# 01_Touch_Sensing_Keys.net
KiCad netlist of a schematic drawn in Altium Designer
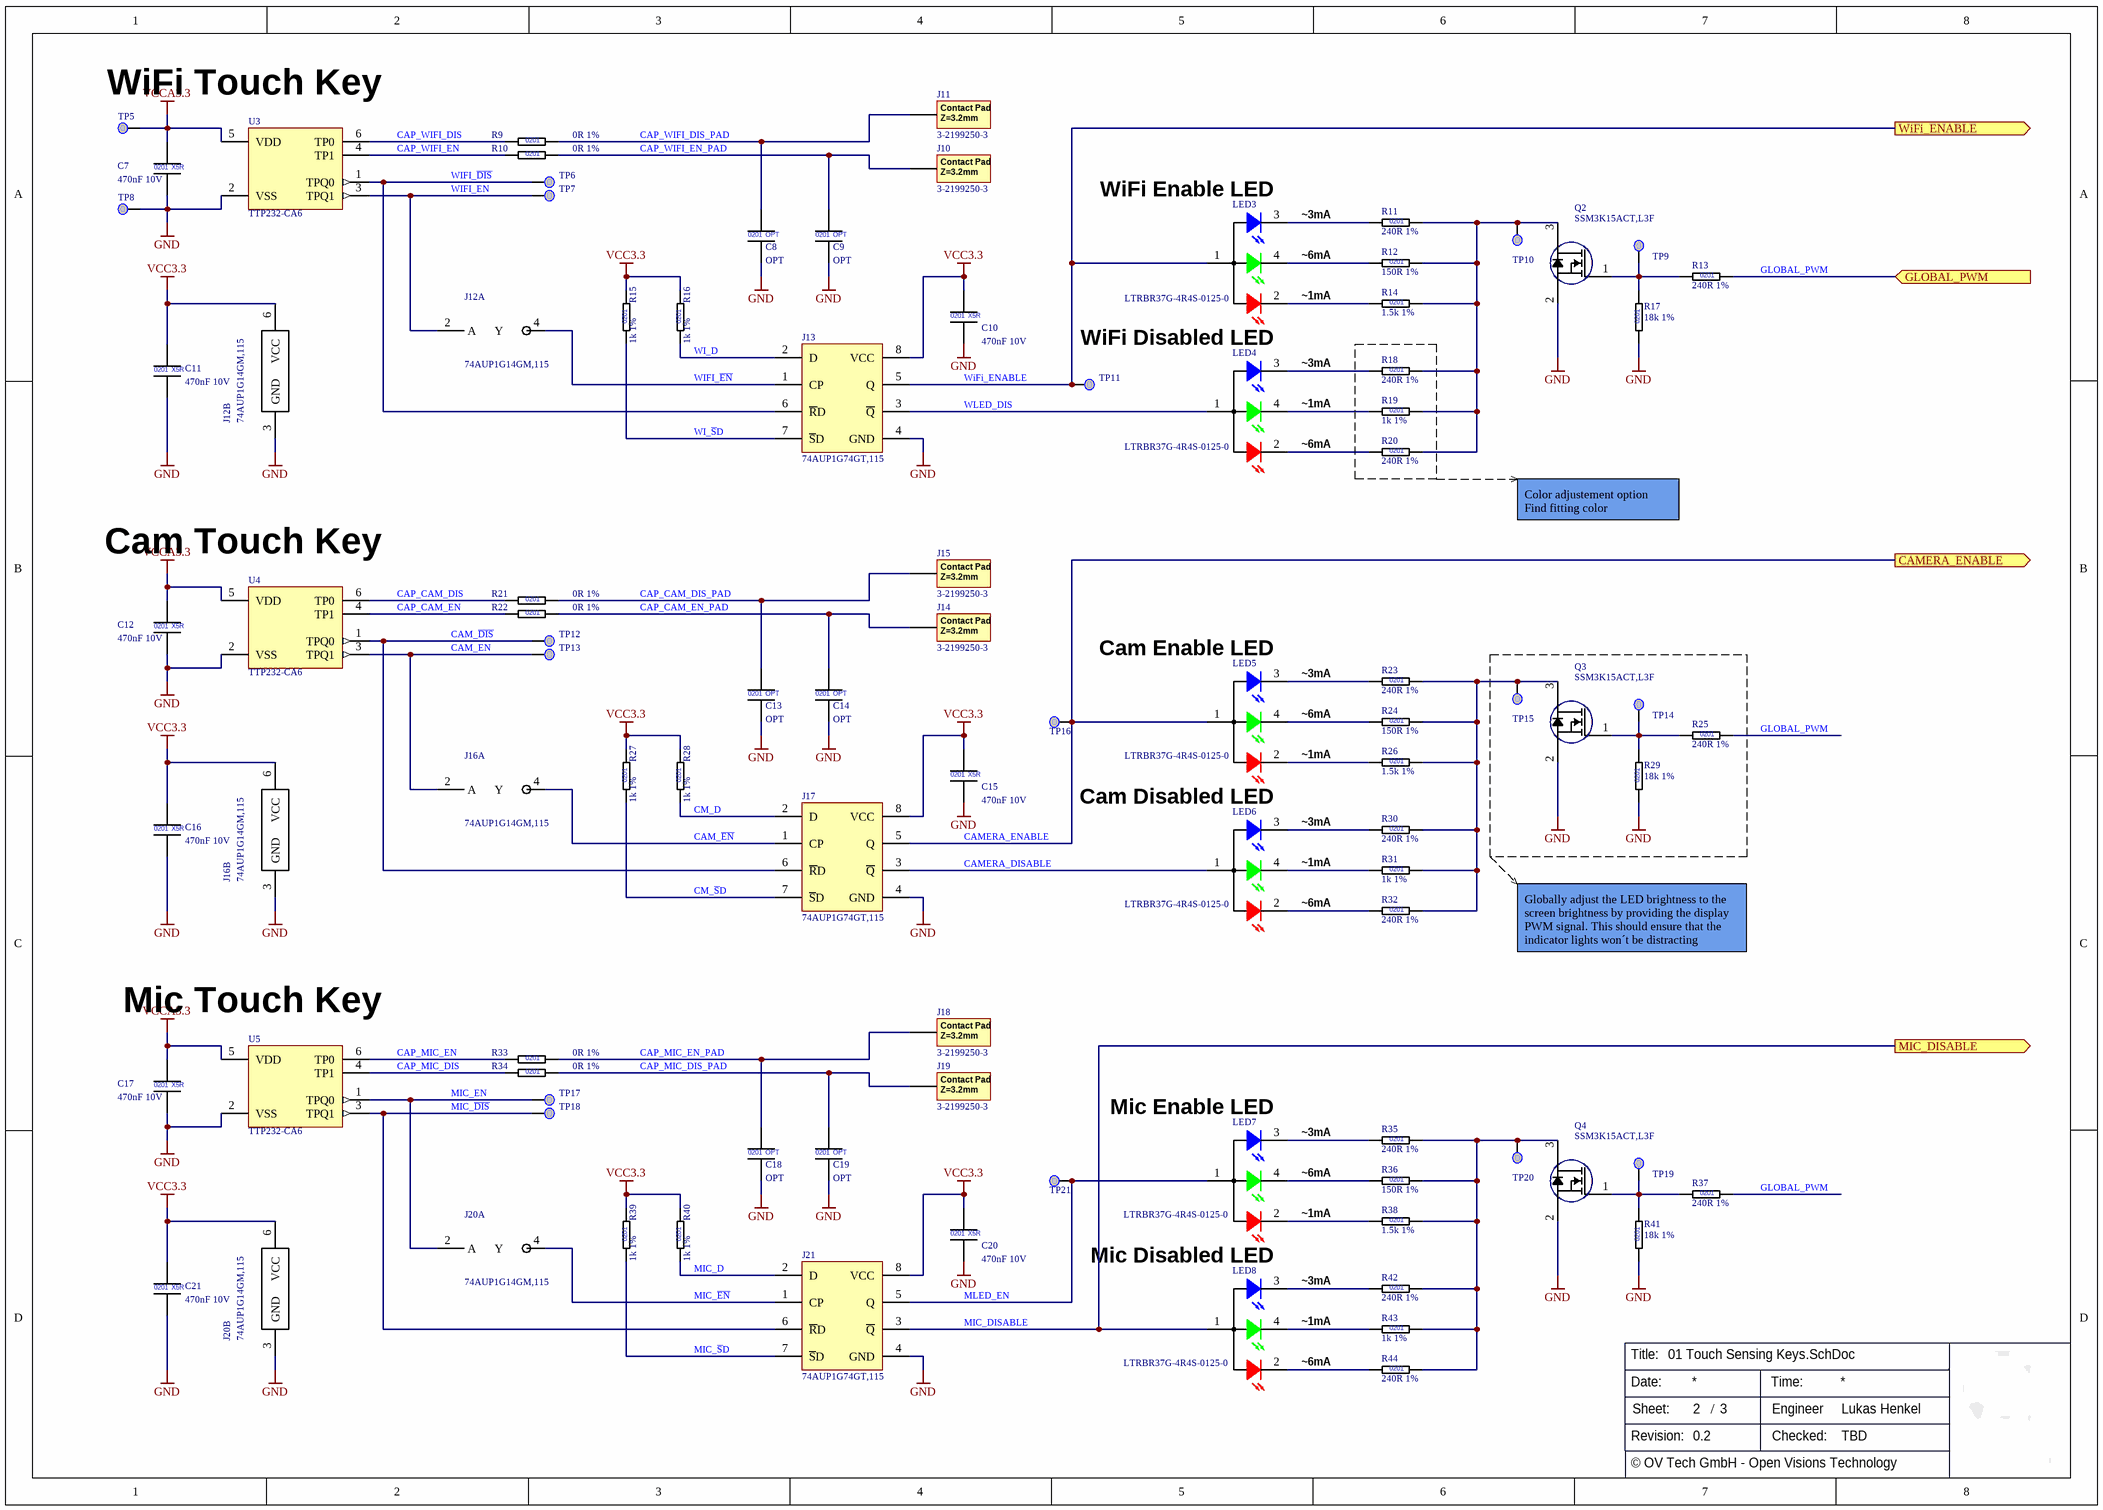
[diagram p0: 01 Touch Sensing Keys.SchDoc]

(export (version "E")
  (design (tool "Eeschema 10.0.6"))
  (components
    (comp (ref "C7")
      (value "470nF 10V")
      (footprint "QV_Cap:CAPC0603X03L")
      (description "Multilayer Ceramic Capacitors MLCC - SMD/SMT 0201 10VDC")
      (libsource (lib "QV_Cap") (part "CAP_0201_470nF_10V"))
    )
    (comp (ref "C8")
      (value "OPT")
      (footprint "QV_Cap:CAPC0603X03L")
      (description "Optional Capacitor 0201")
      (libsource (lib "QV_Cap") (part "CAP_0201_OPT"))
    )
    (comp (ref "C9")
      (value "OPT")
      (footprint "QV_Cap:CAPC0603X03L")
      (description "Optional Capacitor 0201")
      (libsource (lib "QV_Cap") (part "CAP_0201_OPT"))
    )
    (comp (ref "C10")
      (value "470nF 10V")
      (footprint "QV_Cap:CAPC0603X03L")
      (description "Multilayer Ceramic Capacitors MLCC - SMD/SMT 0201 10VDC")
      (libsource (lib "QV_Cap") (part "CAP_0201_470nF_10V"))
    )
    (comp (ref "C11")
      (value "470nF 10V")
      (footprint "QV_Cap:CAPC0603X03L")
      (description "Multilayer Ceramic Capacitors MLCC - SMD/SMT 0201 10VDC")
      (libsource (lib "QV_Cap") (part "CAP_0201_470nF_10V"))
    )
    (comp (ref "C12")
      (value "470nF 10V")
      (footprint "QV_Cap:CAPC0603X03L")
      (description "Multilayer Ceramic Capacitors MLCC - SMD/SMT 0201 10VDC")
      (libsource (lib "QV_Cap") (part "CAP_0201_470nF_10V"))
    )
    (comp (ref "C13")
      (value "OPT")
      (footprint "QV_Cap:CAPC0603X03L")
      (description "Optional Capacitor 0201")
      (libsource (lib "QV_Cap") (part "CAP_0201_OPT"))
    )
    (comp (ref "C14")
      (value "OPT")
      (footprint "QV_Cap:CAPC0603X03L")
      (description "Optional Capacitor 0201")
      (libsource (lib "QV_Cap") (part "CAP_0201_OPT"))
    )
    (comp (ref "C15")
      (value "470nF 10V")
      (footprint "QV_Cap:CAPC0603X03L")
      (description "Multilayer Ceramic Capacitors MLCC - SMD/SMT 0201 10VDC")
      (libsource (lib "QV_Cap") (part "CAP_0201_470nF_10V"))
    )
    (comp (ref "C16")
      (value "470nF 10V")
      (footprint "QV_Cap:CAPC0603X03L")
      (description "Multilayer Ceramic Capacitors MLCC - SMD/SMT 0201 10VDC")
      (libsource (lib "QV_Cap") (part "CAP_0201_470nF_10V"))
    )
    (comp (ref "C17")
      (value "470nF 10V")
      (footprint "QV_Cap:CAPC0603X03L")
      (description "Multilayer Ceramic Capacitors MLCC - SMD/SMT 0201 10VDC")
      (libsource (lib "QV_Cap") (part "CAP_0201_470nF_10V"))
    )
    (comp (ref "C18")
      (value "OPT")
      (footprint "QV_Cap:CAPC0603X03L")
      (description "Optional Capacitor 0201")
      (libsource (lib "QV_Cap") (part "CAP_0201_OPT"))
    )
    (comp (ref "C19")
      (value "OPT")
      (footprint "QV_Cap:CAPC0603X03L")
      (description "Optional Capacitor 0201")
      (libsource (lib "QV_Cap") (part "CAP_0201_OPT"))
    )
    (comp (ref "C20")
      (value "470nF 10V")
      (footprint "QV_Cap:CAPC0603X03L")
      (description "Multilayer Ceramic Capacitors MLCC - SMD/SMT 0201 10VDC")
      (libsource (lib "QV_Cap") (part "CAP_0201_470nF_10V"))
    )
    (comp (ref "C21")
      (value "470nF 10V")
      (footprint "QV_Cap:CAPC0603X03L")
      (description "Multilayer Ceramic Capacitors MLCC - SMD/SMT 0201 10VDC")
      (libsource (lib "QV_Cap") (part "CAP_0201_470nF_10V"))
    )
    (comp (ref "J10")
      (value "3-2199250-3")
      (footprint "QV_ElectroMech:Contact Pad_3.2mm_3-2199250-3")
      (description "SMD Contact pad spring loaded 3.2mm")
      (libsource (lib "QV_ElectroMech") (part "PAD_3-2199250-3"))
    )
    (comp (ref "J11")
      (value "3-2199250-3")
      (footprint "QV_ElectroMech:Contact Pad_3.2mm_3-2199250-3")
      (description "SMD Contact pad spring loaded 3.2mm")
      (libsource (lib "QV_ElectroMech") (part "PAD_3-2199250-3"))
    )
    (comp (ref "J12")
      (value "74AUP1G14GM,115")
      (footprint "QV_Digital:PSON50P140X100X50-6L")
      (description "Single Unbuffered Inverter 74AUP1G14GM,115")
      (libsource (lib "QV_Digital") (part "Inverter_74AUP1G14GM,115"))
    )
    (comp (ref "J13")
      (value "74AUP1G74GT,115")
      (footprint "QV_Digital:PSON50P100X50-8L")
      (description "D-type flip-flop with differential output and async set- and reset input")
      (libsource (lib "QV_Digital") (part "D-FLOP_SMG-W-2,0x1,2x1,25-AU"))
    )
    (comp (ref "J14")
      (value "3-2199250-3")
      (footprint "QV_ElectroMech:Contact Pad_3.2mm_3-2199250-3")
      (description "SMD Contact pad spring loaded 3.2mm")
      (libsource (lib "QV_ElectroMech") (part "PAD_3-2199250-3"))
    )
    (comp (ref "J15")
      (value "3-2199250-3")
      (footprint "QV_ElectroMech:Contact Pad_3.2mm_3-2199250-3")
      (description "SMD Contact pad spring loaded 3.2mm")
      (libsource (lib "QV_ElectroMech") (part "PAD_3-2199250-3"))
    )
    (comp (ref "J16")
      (value "74AUP1G14GM,115")
      (footprint "QV_Digital:PSON50P140X100X50-6L")
      (description "Single Unbuffered Inverter 74AUP1G14GM,115")
      (libsource (lib "QV_Digital") (part "Inverter_74AUP1G14GM,115"))
    )
    (comp (ref "J17")
      (value "74AUP1G74GT,115")
      (footprint "QV_Digital:PSON50P100X50-8L")
      (description "D-type flip-flop with differential output and async set- and reset input")
      (libsource (lib "QV_Digital") (part "D-FLOP_SMG-W-2,0x1,2x1,25-AU"))
    )
    (comp (ref "J18")
      (value "3-2199250-3")
      (footprint "QV_ElectroMech:Contact Pad_3.2mm_3-2199250-3")
      (description "SMD Contact pad spring loaded 3.2mm")
      (libsource (lib "QV_ElectroMech") (part "PAD_3-2199250-3"))
    )
    (comp (ref "J19")
      (value "3-2199250-3")
      (footprint "QV_ElectroMech:Contact Pad_3.2mm_3-2199250-3")
      (description "SMD Contact pad spring loaded 3.2mm")
      (libsource (lib "QV_ElectroMech") (part "PAD_3-2199250-3"))
    )
    (comp (ref "J20")
      (value "74AUP1G14GM,115")
      (footprint "QV_Digital:PSON50P140X100X50-6L")
      (description "Single Unbuffered Inverter 74AUP1G14GM,115")
      (libsource (lib "QV_Digital") (part "Inverter_74AUP1G14GM,115"))
    )
    (comp (ref "J21")
      (value "74AUP1G74GT,115")
      (footprint "QV_Digital:PSON50P100X50-8L")
      (description "D-type flip-flop with differential output and async set- and reset input")
      (libsource (lib "QV_Digital") (part "D-FLOP_SMG-W-2,0x1,2x1,25-AU"))
    )
    (comp (ref "LED3")
      (value "LTRBR37G-4R4S-0125-0")
      (footprint "QV_LED:LED 120X120 LTRB R37G RGB")
      (description "Micro LED Ultra Low Profile 1.2mm X 1.2mm X 0.25mm LTRBR37G")
      (libsource (lib "QV_LED") (part "LED RGB Low Profile_LTRBR37G-4R4S-0125-0"))
    )
    (comp (ref "LED4")
      (value "LTRBR37G-4R4S-0125-0")
      (footprint "QV_LED:LED 120X120 LTRB R37G RGB")
      (description "Micro LED Ultra Low Profile 1.2mm X 1.2mm X 0.25mm LTRBR37G")
      (libsource (lib "QV_LED") (part "LED RGB Low Profile_LTRBR37G-4R4S-0125-0"))
    )
    (comp (ref "LED5")
      (value "LTRBR37G-4R4S-0125-0")
      (footprint "QV_LED:LED 120X120 LTRB R37G RGB")
      (description "Micro LED Ultra Low Profile 1.2mm X 1.2mm X 0.25mm LTRBR37G")
      (libsource (lib "QV_LED") (part "LED RGB Low Profile_LTRBR37G-4R4S-0125-0"))
    )
    (comp (ref "LED6")
      (value "LTRBR37G-4R4S-0125-0")
      (footprint "QV_LED:LED 120X120 LTRB R37G RGB")
      (description "Micro LED Ultra Low Profile 1.2mm X 1.2mm X 0.25mm LTRBR37G")
      (libsource (lib "QV_LED") (part "LED RGB Low Profile_LTRBR37G-4R4S-0125-0"))
    )
    (comp (ref "LED7")
      (value "LTRBR37G-4R4S-0125-0")
      (footprint "QV_LED:LED 120X120 LTRB R37G RGB")
      (description "Micro LED Ultra Low Profile 1.2mm X 1.2mm X 0.25mm LTRBR37G")
      (libsource (lib "QV_LED") (part "LED RGB Low Profile_LTRBR37G-4R4S-0125-0"))
    )
    (comp (ref "LED8")
      (value "LTRBR37G-4R4S-0125-0")
      (footprint "QV_LED:LED 120X120 LTRB R37G RGB")
      (description "Micro LED Ultra Low Profile 1.2mm X 1.2mm X 0.25mm LTRBR37G")
      (libsource (lib "QV_LED") (part "LED RGB Low Profile_LTRBR37G-4R4S-0125-0"))
    )
    (comp (ref "Q2")
      (value "SSM3K15ACT,L3F")
      (footprint "QV_Trans:DFN65P100X50-3L")
      (description "MOSFET 30V SGL N-CH TRENCHMOS Logic Level")
      (libsource (lib "QV_Trans") (part "N-Channel MOSFET_SSM3K15ACT,L3F"))
    )
    (comp (ref "Q3")
      (value "SSM3K15ACT,L3F")
      (footprint "QV_Trans:DFN65P100X50-3L")
      (description "MOSFET 30V SGL N-CH TRENCHMOS Logic Level")
      (libsource (lib "QV_Trans") (part "N-Channel MOSFET_SSM3K15ACT,L3F"))
    )
    (comp (ref "Q4")
      (value "SSM3K15ACT,L3F")
      (footprint "QV_Trans:DFN65P100X50-3L")
      (description "MOSFET 30V SGL N-CH TRENCHMOS Logic Level")
      (libsource (lib "QV_Trans") (part "N-Channel MOSFET_SSM3K15ACT,L3F"))
    )
    (comp (ref "R9")
      (value "0R 1%")
      (footprint "QV_Res:RESC0603X03L")
      (description "Thick Film Resistors - SMD 0R OHM 1%")
      (libsource (lib "QV_res") (part "RES_0201_0R_1%"))
    )
    (comp (ref "R10")
      (value "0R 1%")
      (footprint "QV_Res:RESC0603X03L")
      (description "Thick Film Resistors - SMD 0R OHM 1%")
      (libsource (lib "QV_res") (part "RES_0201_0R_1%"))
    )
    (comp (ref "R11")
      (value "240R 1%")
      (footprint "QV_Res:RESC0603X03L")
      (description "Thick Film Resistors - SMD 240 OHM 1%")
      (libsource (lib "QV_res") (part "RES_0201_240R_1%"))
    )
    (comp (ref "R12")
      (value "150R 1%")
      (footprint "QV_Res:RESC0603X03L")
      (description "Thick Film Resistors - SMD 150 OHM 1%")
      (libsource (lib "QV_res") (part "RES_0201_150R_1%"))
    )
    (comp (ref "R13")
      (value "240R 1%")
      (footprint "QV_Res:RESC0603X03L")
      (description "Thick Film Resistors - SMD 240 OHM 1%")
      (libsource (lib "QV_res") (part "RES_0201_240R_1%"))
    )
    (comp (ref "R14")
      (value "1.5k 1%")
      (footprint "QV_Res:RESC0603X03L")
      (description "Thick Film Resistors - SMD 1.5K OHM 1%")
      (libsource (lib "QV_res") (part "RES_0201_1.5k_1%"))
    )
    (comp (ref "R15")
      (value "1k 1%")
      (footprint "QV_Res:RESC0603X03L")
      (description "Thick Film Resistors - SMD 1K OHM 1%")
      (libsource (lib "QV_res") (part "RES_0201_1k_1%"))
    )
    (comp (ref "R16")
      (value "1k 1%")
      (footprint "QV_Res:RESC0603X03L")
      (description "Thick Film Resistors - SMD 1K OHM 1%")
      (libsource (lib "QV_res") (part "RES_0201_1k_1%"))
    )
    (comp (ref "R17")
      (value "18k 1%")
      (footprint "QV_Res:RESC0603X03L")
      (description "Thick Film Resistors - SMD 18K OHM 1%")
      (libsource (lib "QV_res") (part "RES_0201_18k_1%"))
    )
    (comp (ref "R18")
      (value "240R 1%")
      (footprint "QV_Res:RESC0603X03L")
      (description "Thick Film Resistors - SMD 240 OHM 1%")
      (libsource (lib "QV_res") (part "RES_0201_240R_1%"))
    )
    (comp (ref "R19")
      (value "1k 1%")
      (footprint "QV_Res:RESC0603X03L")
      (description "Thick Film Resistors - SMD 1K OHM 1%")
      (libsource (lib "QV_res") (part "RES_0201_1k_1%"))
    )
    (comp (ref "R20")
      (value "240R 1%")
      (footprint "QV_Res:RESC0603X03L")
      (description "Thick Film Resistors - SMD 240 OHM 1%")
      (libsource (lib "QV_res") (part "RES_0201_240R_1%"))
    )
    (comp (ref "R21")
      (value "0R 1%")
      (footprint "QV_Res:RESC0603X03L")
      (description "Thick Film Resistors - SMD 0R OHM 1%")
      (libsource (lib "QV_res") (part "RES_0201_0R_1%"))
    )
    (comp (ref "R22")
      (value "0R 1%")
      (footprint "QV_Res:RESC0603X03L")
      (description "Thick Film Resistors - SMD 0R OHM 1%")
      (libsource (lib "QV_res") (part "RES_0201_0R_1%"))
    )
    (comp (ref "R23")
      (value "240R 1%")
      (footprint "QV_Res:RESC0603X03L")
      (description "Thick Film Resistors - SMD 240 OHM 1%")
      (libsource (lib "QV_res") (part "RES_0201_240R_1%"))
    )
    (comp (ref "R24")
      (value "150R 1%")
      (footprint "QV_Res:RESC0603X03L")
      (description "Thick Film Resistors - SMD 150 OHM 1%")
      (libsource (lib "QV_res") (part "RES_0201_150R_1%"))
    )
    (comp (ref "R25")
      (value "240R 1%")
      (footprint "QV_Res:RESC0603X03L")
      (description "Thick Film Resistors - SMD 240 OHM 1%")
      (libsource (lib "QV_res") (part "RES_0201_240R_1%"))
    )
    (comp (ref "R26")
      (value "1.5k 1%")
      (footprint "QV_Res:RESC0603X03L")
      (description "Thick Film Resistors - SMD 1.5K OHM 1%")
      (libsource (lib "QV_res") (part "RES_0201_1.5k_1%"))
    )
    (comp (ref "R27")
      (value "1k 1%")
      (footprint "QV_Res:RESC0603X03L")
      (description "Thick Film Resistors - SMD 1K OHM 1%")
      (libsource (lib "QV_res") (part "RES_0201_1k_1%"))
    )
    (comp (ref "R28")
      (value "1k 1%")
      (footprint "QV_Res:RESC0603X03L")
      (description "Thick Film Resistors - SMD 1K OHM 1%")
      (libsource (lib "QV_res") (part "RES_0201_1k_1%"))
    )
    (comp (ref "R29")
      (value "18k 1%")
      (footprint "QV_Res:RESC0603X03L")
      (description "Thick Film Resistors - SMD 18K OHM 1%")
      (libsource (lib "QV_res") (part "RES_0201_18k_1%"))
    )
    (comp (ref "R30")
      (value "240R 1%")
      (footprint "QV_Res:RESC0603X03L")
      (description "Thick Film Resistors - SMD 240 OHM 1%")
      (libsource (lib "QV_res") (part "RES_0201_240R_1%"))
    )
    (comp (ref "R31")
      (value "1k 1%")
      (footprint "QV_Res:RESC0603X03L")
      (description "Thick Film Resistors - SMD 1K OHM 1%")
      (libsource (lib "QV_res") (part "RES_0201_1k_1%"))
    )
    (comp (ref "R32")
      (value "240R 1%")
      (footprint "QV_Res:RESC0603X03L")
      (description "Thick Film Resistors - SMD 240 OHM 1%")
      (libsource (lib "QV_res") (part "RES_0201_240R_1%"))
    )
    (comp (ref "R33")
      (value "0R 1%")
      (footprint "QV_Res:RESC0603X03L")
      (description "Thick Film Resistors - SMD 0R OHM 1%")
      (libsource (lib "QV_res") (part "RES_0201_0R_1%"))
    )
    (comp (ref "R34")
      (value "0R 1%")
      (footprint "QV_Res:RESC0603X03L")
      (description "Thick Film Resistors - SMD 0R OHM 1%")
      (libsource (lib "QV_res") (part "RES_0201_0R_1%"))
    )
    (comp (ref "R35")
      (value "240R 1%")
      (footprint "QV_Res:RESC0603X03L")
      (description "Thick Film Resistors - SMD 240 OHM 1%")
      (libsource (lib "QV_res") (part "RES_0201_240R_1%"))
    )
    (comp (ref "R36")
      (value "150R 1%")
      (footprint "QV_Res:RESC0603X03L")
      (description "Thick Film Resistors - SMD 150 OHM 1%")
      (libsource (lib "QV_res") (part "RES_0201_150R_1%"))
    )
    (comp (ref "R37")
      (value "240R 1%")
      (footprint "QV_Res:RESC0603X03L")
      (description "Thick Film Resistors - SMD 240 OHM 1%")
      (libsource (lib "QV_res") (part "RES_0201_240R_1%"))
    )
    (comp (ref "R38")
      (value "1.5k 1%")
      (footprint "QV_Res:RESC0603X03L")
      (description "Thick Film Resistors - SMD 1.5K OHM 1%")
      (libsource (lib "QV_res") (part "RES_0201_1.5k_1%"))
    )
    (comp (ref "R39")
      (value "1k 1%")
      (footprint "QV_Res:RESC0603X03L")
      (description "Thick Film Resistors - SMD 1K OHM 1%")
      (libsource (lib "QV_res") (part "RES_0201_1k_1%"))
    )
    (comp (ref "R40")
      (value "1k 1%")
      (footprint "QV_Res:RESC0603X03L")
      (description "Thick Film Resistors - SMD 1K OHM 1%")
      (libsource (lib "QV_res") (part "RES_0201_1k_1%"))
    )
    (comp (ref "R41")
      (value "18k 1%")
      (footprint "QV_Res:RESC0603X03L")
      (description "Thick Film Resistors - SMD 18K OHM 1%")
      (libsource (lib "QV_res") (part "RES_0201_18k_1%"))
    )
    (comp (ref "R42")
      (value "240R 1%")
      (footprint "QV_Res:RESC0603X03L")
      (description "Thick Film Resistors - SMD 240 OHM 1%")
      (libsource (lib "QV_res") (part "RES_0201_240R_1%"))
    )
    (comp (ref "R43")
      (value "1k 1%")
      (footprint "QV_Res:RESC0603X03L")
      (description "Thick Film Resistors - SMD 1K OHM 1%")
      (libsource (lib "QV_res") (part "RES_0201_1k_1%"))
    )
    (comp (ref "R44")
      (value "240R 1%")
      (footprint "QV_Res:RESC0603X03L")
      (description "Thick Film Resistors - SMD 240 OHM 1%")
      (libsource (lib "QV_res") (part "RES_0201_240R_1%"))
    )
    (comp (ref "TP5")
      (value "Testpoint 0.5mm")
      (footprint "QV_ElectroMech:TP_0.50mm")
      (libsource (lib "QV_ElectroMech") (part "Testpoint 0.5mm"))
    )
    (comp (ref "TP6")
      (value "Testpoint 0.5mm")
      (footprint "QV_ElectroMech:TP_0.50mm")
      (libsource (lib "QV_ElectroMech") (part "Testpoint 0.5mm"))
    )
    (comp (ref "TP7")
      (value "Testpoint 0.5mm")
      (footprint "QV_ElectroMech:TP_0.50mm")
      (libsource (lib "QV_ElectroMech") (part "Testpoint 0.5mm"))
    )
    (comp (ref "TP8")
      (value "Testpoint 0.5mm")
      (footprint "QV_ElectroMech:TP_0.50mm")
      (libsource (lib "QV_ElectroMech") (part "Testpoint 0.5mm"))
    )
    (comp (ref "TP9")
      (value "Testpoint 0.5mm")
      (footprint "QV_ElectroMech:TP_0.50mm")
      (libsource (lib "QV_ElectroMech") (part "Testpoint 0.5mm"))
    )
    (comp (ref "TP10")
      (value "Testpoint 0.5mm")
      (footprint "QV_ElectroMech:TP_0.50mm")
      (libsource (lib "QV_ElectroMech") (part "Testpoint 0.5mm"))
    )
    (comp (ref "TP11")
      (value "Testpoint 0.5mm")
      (footprint "QV_ElectroMech:TP_0.50mm")
      (libsource (lib "QV_ElectroMech") (part "Testpoint 0.5mm"))
    )
    (comp (ref "TP12")
      (value "Testpoint 0.5mm")
      (footprint "QV_ElectroMech:TP_0.50mm")
      (libsource (lib "QV_ElectroMech") (part "Testpoint 0.5mm"))
    )
    (comp (ref "TP13")
      (value "Testpoint 0.5mm")
      (footprint "QV_ElectroMech:TP_0.50mm")
      (libsource (lib "QV_ElectroMech") (part "Testpoint 0.5mm"))
    )
    (comp (ref "TP14")
      (value "Testpoint 0.5mm")
      (footprint "QV_ElectroMech:TP_0.50mm")
      (libsource (lib "QV_ElectroMech") (part "Testpoint 0.5mm"))
    )
    (comp (ref "TP15")
      (value "Testpoint 0.5mm")
      (footprint "QV_ElectroMech:TP_0.50mm")
      (libsource (lib "QV_ElectroMech") (part "Testpoint 0.5mm"))
    )
    (comp (ref "TP16")
      (value "Testpoint 0.5mm")
      (footprint "QV_ElectroMech:TP_0.50mm")
      (libsource (lib "QV_ElectroMech") (part "Testpoint 0.5mm"))
    )
    (comp (ref "TP17")
      (value "Testpoint 0.5mm")
      (footprint "QV_ElectroMech:TP_0.50mm")
      (libsource (lib "QV_ElectroMech") (part "Testpoint 0.5mm"))
    )
    (comp (ref "TP18")
      (value "Testpoint 0.5mm")
      (footprint "QV_ElectroMech:TP_0.50mm")
      (libsource (lib "QV_ElectroMech") (part "Testpoint 0.5mm"))
    )
    (comp (ref "TP19")
      (value "Testpoint 0.5mm")
      (footprint "QV_ElectroMech:TP_0.50mm")
      (libsource (lib "QV_ElectroMech") (part "Testpoint 0.5mm"))
    )
    (comp (ref "TP20")
      (value "Testpoint 0.5mm")
      (footprint "QV_ElectroMech:TP_0.50mm")
      (libsource (lib "QV_ElectroMech") (part "Testpoint 0.5mm"))
    )
    (comp (ref "TP21")
      (value "Testpoint 0.5mm")
      (footprint "QV_ElectroMech:TP_0.50mm")
      (libsource (lib "QV_ElectroMech") (part "Testpoint 0.5mm"))
    )
    (comp (ref "U3")
      (value "TTP232-CA6")
      (footprint "QV_Active:SOT95P285X126-6L")
      (description "Two key touch pad detector IC TTP232-CA6")
      (libsource (lib "QV_Active") (part "Dual key capacitive touch sensing_TTP232-CA6"))
    )
    (comp (ref "U4")
      (value "TTP232-CA6")
      (footprint "QV_Active:SOT95P285X126-6L")
      (description "Two key touch pad detector IC TTP232-CA6")
      (libsource (lib "QV_Active") (part "Dual key capacitive touch sensing_TTP232-CA6"))
    )
    (comp (ref "U5")
      (value "TTP232-CA6")
      (footprint "QV_Active:SOT95P285X126-6L")
      (description "Two key touch pad detector IC TTP232-CA6")
      (libsource (lib "QV_Active") (part "Dual key capacitive touch sensing_TTP232-CA6"))
    )
  )
  (nets
    (net (code "1") (name "/CAMERA_DISABLE") (class "Default")
      (node (ref "J17") (pin "3") (pinfunction "~{Q}_3") (pintype "passive"))
      (node (ref "LED6") (pin "1") (pinfunction "1_1") (pintype "passive"))
    )
    (net (code "2") (name "/CAMERA_ENABLE") (class "Default")
      (node (ref "J17") (pin "5") (pinfunction "Q_5") (pintype "passive"))
      (node (ref "LED5") (pin "1") (pinfunction "1_1") (pintype "passive"))
      (node (ref "TP16") (pin "TP") (pinfunction "TP_TP") (pintype "passive"))
    )
    (net (code "3") (name "/CAM_EN") (class "Default")
      (node (ref "J16") (pin "2") (pinfunction "A_2") (pintype "passive"))
      (node (ref "TP13") (pin "TP") (pinfunction "TP_TP") (pintype "passive"))
      (node (ref "U4") (pin "3") (pinfunction "TPQ1_3") (pintype "output"))
    )
    (net (code "4") (name "/CAM_~{DIS}") (class "Default")
      (node (ref "J17") (pin "6") (pinfunction "~{R}D_6") (pintype "passive"))
      (node (ref "TP12") (pin "TP") (pinfunction "TP_TP") (pintype "passive"))
      (node (ref "U4") (pin "1") (pinfunction "TPQ0_1") (pintype "output"))
    )
    (net (code "5") (name "/CAM_~{EN}") (class "Default")
      (node (ref "J16") (pin "4") (pinfunction "Y_4") (pintype "passive"))
      (node (ref "J17") (pin "1") (pinfunction "CP_1") (pintype "passive"))
    )
    (net (code "6") (name "/CAP_CAM_DIS") (class "Default")
      (node (ref "R21") (pin "1") (pinfunction "1_1") (pintype "passive"))
      (node (ref "U4") (pin "6") (pinfunction "TP0_6") (pintype "passive"))
    )
    (net (code "7") (name "/CAP_CAM_DIS_PAD") (class "Default")
      (node (ref "C13") (pin "1") (pinfunction "1_1") (pintype "passive"))
      (node (ref "J15") (pin "1") (pinfunction "1_1") (pintype "passive"))
      (node (ref "R21") (pin "2") (pinfunction "2_2") (pintype "passive"))
    )
    (net (code "8") (name "/CAP_CAM_EN") (class "Default")
      (node (ref "R22") (pin "1") (pinfunction "1_1") (pintype "passive"))
      (node (ref "U4") (pin "4") (pinfunction "TP1_4") (pintype "passive"))
    )
    (net (code "9") (name "/CAP_CAM_EN_PAD") (class "Default")
      (node (ref "C14") (pin "1") (pinfunction "1_1") (pintype "passive"))
      (node (ref "J14") (pin "1") (pinfunction "1_1") (pintype "passive"))
      (node (ref "R22") (pin "2") (pinfunction "2_2") (pintype "passive"))
    )
    (net (code "10") (name "/CAP_MIC_DIS") (class "Default")
      (node (ref "R34") (pin "1") (pinfunction "1_1") (pintype "passive"))
      (node (ref "U5") (pin "4") (pinfunction "TP1_4") (pintype "passive"))
    )
    (net (code "11") (name "/CAP_MIC_DIS_PAD") (class "Default")
      (node (ref "C19") (pin "1") (pinfunction "1_1") (pintype "passive"))
      (node (ref "J19") (pin "1") (pinfunction "1_1") (pintype "passive"))
      (node (ref "R34") (pin "2") (pinfunction "2_2") (pintype "passive"))
    )
    (net (code "12") (name "/CAP_MIC_EN") (class "Default")
      (node (ref "R33") (pin "1") (pinfunction "1_1") (pintype "passive"))
      (node (ref "U5") (pin "6") (pinfunction "TP0_6") (pintype "passive"))
    )
    (net (code "13") (name "/CAP_MIC_EN_PAD") (class "Default")
      (node (ref "C18") (pin "1") (pinfunction "1_1") (pintype "passive"))
      (node (ref "J18") (pin "1") (pinfunction "1_1") (pintype "passive"))
      (node (ref "R33") (pin "2") (pinfunction "2_2") (pintype "passive"))
    )
    (net (code "14") (name "/CAP_WIFI_DIS") (class "Default")
      (node (ref "R9") (pin "1") (pinfunction "1_1") (pintype "passive"))
      (node (ref "U3") (pin "6") (pinfunction "TP0_6") (pintype "passive"))
    )
    (net (code "15") (name "/CAP_WIFI_DIS_PAD") (class "Default")
      (node (ref "C8") (pin "1") (pinfunction "1_1") (pintype "passive"))
      (node (ref "J11") (pin "1") (pinfunction "1_1") (pintype "passive"))
      (node (ref "R9") (pin "2") (pinfunction "2_2") (pintype "passive"))
    )
    (net (code "16") (name "/CAP_WIFI_EN") (class "Default")
      (node (ref "R10") (pin "1") (pinfunction "1_1") (pintype "passive"))
      (node (ref "U3") (pin "4") (pinfunction "TP1_4") (pintype "passive"))
    )
    (net (code "17") (name "/CAP_WIFI_EN_PAD") (class "Default")
      (node (ref "C9") (pin "1") (pinfunction "1_1") (pintype "passive"))
      (node (ref "J10") (pin "1") (pinfunction "1_1") (pintype "passive"))
      (node (ref "R10") (pin "2") (pinfunction "2_2") (pintype "passive"))
    )
    (net (code "18") (name "/CM_D") (class "Default")
      (node (ref "J17") (pin "2") (pinfunction "D_2") (pintype "passive"))
      (node (ref "R28") (pin "1") (pinfunction "1_1") (pintype "passive"))
    )
    (net (code "19") (name "/CM_~{S}D") (class "Default")
      (node (ref "J17") (pin "7") (pinfunction "~{S}D_7") (pintype "passive"))
      (node (ref "R27") (pin "1") (pinfunction "1_1") (pintype "passive"))
    )
    (net (code "20") (name "/GLOBAL_PWM") (class "Default")
      (node (ref "R13") (pin "2") (pinfunction "2_2") (pintype "passive"))
      (node (ref "R25") (pin "2") (pinfunction "2_2") (pintype "passive"))
      (node (ref "R37") (pin "2") (pinfunction "2_2") (pintype "passive"))
    )
    (net (code "21") (name "/MIC_D") (class "Default")
      (node (ref "J21") (pin "2") (pinfunction "D_2") (pintype "passive"))
      (node (ref "R40") (pin "1") (pinfunction "1_1") (pintype "passive"))
    )
    (net (code "22") (name "/MIC_DISABLE") (class "Default")
      (node (ref "J21") (pin "3") (pinfunction "~{Q}_3") (pintype "passive"))
      (node (ref "LED8") (pin "1") (pinfunction "1_1") (pintype "passive"))
    )
    (net (code "23") (name "/MIC_EN") (class "Default")
      (node (ref "J20") (pin "2") (pinfunction "A_2") (pintype "passive"))
      (node (ref "TP17") (pin "TP") (pinfunction "TP_TP") (pintype "passive"))
      (node (ref "U5") (pin "1") (pinfunction "TPQ0_1") (pintype "output"))
    )
    (net (code "24") (name "/MIC_~{DIS}") (class "Default")
      (node (ref "J21") (pin "6") (pinfunction "~{R}D_6") (pintype "passive"))
      (node (ref "TP18") (pin "TP") (pinfunction "TP_TP") (pintype "passive"))
      (node (ref "U5") (pin "3") (pinfunction "TPQ1_3") (pintype "output"))
    )
    (net (code "25") (name "/MIC_~{EN}") (class "Default")
      (node (ref "J20") (pin "4") (pinfunction "Y_4") (pintype "passive"))
      (node (ref "J21") (pin "1") (pinfunction "CP_1") (pintype "passive"))
    )
    (net (code "26") (name "/MIC_~{S}D") (class "Default")
      (node (ref "J21") (pin "7") (pinfunction "~{S}D_7") (pintype "passive"))
      (node (ref "R39") (pin "1") (pinfunction "1_1") (pintype "passive"))
    )
    (net (code "27") (name "/MLED_EN") (class "Default")
      (node (ref "J21") (pin "5") (pinfunction "Q_5") (pintype "passive"))
      (node (ref "LED7") (pin "1") (pinfunction "1_1") (pintype "passive"))
      (node (ref "TP21") (pin "TP") (pinfunction "TP_TP") (pintype "passive"))
    )
    (net (code "28") (name "/WIFI_EN") (class "Default")
      (node (ref "J12") (pin "2") (pinfunction "A_2") (pintype "passive"))
      (node (ref "TP7") (pin "TP") (pinfunction "TP_TP") (pintype "passive"))
      (node (ref "U3") (pin "3") (pinfunction "TPQ1_3") (pintype "output"))
    )
    (net (code "29") (name "/WIFI_~{DIS}") (class "Default")
      (node (ref "J13") (pin "6") (pinfunction "~{R}D_6") (pintype "passive"))
      (node (ref "TP6") (pin "TP") (pinfunction "TP_TP") (pintype "passive"))
      (node (ref "U3") (pin "1") (pinfunction "TPQ0_1") (pintype "output"))
    )
    (net (code "30") (name "/WIFI_~{EN}") (class "Default")
      (node (ref "J12") (pin "4") (pinfunction "Y_4") (pintype "passive"))
      (node (ref "J13") (pin "1") (pinfunction "CP_1") (pintype "passive"))
    )
    (net (code "31") (name "/WI_D") (class "Default")
      (node (ref "J13") (pin "2") (pinfunction "D_2") (pintype "passive"))
      (node (ref "R16") (pin "1") (pinfunction "1_1") (pintype "passive"))
    )
    (net (code "32") (name "/WI_~{S}D") (class "Default")
      (node (ref "J13") (pin "7") (pinfunction "~{S}D_7") (pintype "passive"))
      (node (ref "R15") (pin "1") (pinfunction "1_1") (pintype "passive"))
    )
    (net (code "33") (name "/WLED_DIS") (class "Default")
      (node (ref "J13") (pin "3") (pinfunction "~{Q}_3") (pintype "passive"))
      (node (ref "LED4") (pin "1") (pinfunction "1_1") (pintype "passive"))
    )
    (net (code "34") (name "/WiFi_ENABLE") (class "Default")
      (node (ref "J13") (pin "5") (pinfunction "Q_5") (pintype "passive"))
      (node (ref "LED3") (pin "1") (pinfunction "1_1") (pintype "passive"))
      (node (ref "TP11") (pin "TP") (pinfunction "TP_TP") (pintype "passive"))
    )
    (net (code "35") (name "GND") (class "Default")
      (node (ref "C10") (pin "2") (pinfunction "2_2") (pintype "passive"))
      (node (ref "C11") (pin "2") (pinfunction "2_2") (pintype "passive"))
      (node (ref "C12") (pin "2") (pinfunction "2_2") (pintype "passive"))
      (node (ref "C13") (pin "2") (pinfunction "2_2") (pintype "passive"))
      (node (ref "C14") (pin "2") (pinfunction "2_2") (pintype "passive"))
      (node (ref "C15") (pin "2") (pinfunction "2_2") (pintype "passive"))
      (node (ref "C16") (pin "2") (pinfunction "2_2") (pintype "passive"))
      (node (ref "C17") (pin "2") (pinfunction "2_2") (pintype "passive"))
      (node (ref "C18") (pin "2") (pinfunction "2_2") (pintype "passive"))
      (node (ref "C19") (pin "2") (pinfunction "2_2") (pintype "passive"))
      (node (ref "C20") (pin "2") (pinfunction "2_2") (pintype "passive"))
      (node (ref "C21") (pin "2") (pinfunction "2_2") (pintype "passive"))
      (node (ref "C7") (pin "2") (pinfunction "2_2") (pintype "passive"))
      (node (ref "C8") (pin "2") (pinfunction "2_2") (pintype "passive"))
      (node (ref "C9") (pin "2") (pinfunction "2_2") (pintype "passive"))
      (node (ref "J12") (pin "3") (pinfunction "GND_3") (pintype "passive"))
      (node (ref "J13") (pin "4") (pinfunction "GND_4") (pintype "passive"))
      (node (ref "J16") (pin "3") (pinfunction "GND_3") (pintype "passive"))
      (node (ref "J17") (pin "4") (pinfunction "GND_4") (pintype "passive"))
      (node (ref "J20") (pin "3") (pinfunction "GND_3") (pintype "passive"))
      (node (ref "J21") (pin "4") (pinfunction "GND_4") (pintype "passive"))
      (node (ref "Q2") (pin "2") (pinfunction "S_2") (pintype "passive"))
      (node (ref "Q3") (pin "2") (pinfunction "S_2") (pintype "passive"))
      (node (ref "Q4") (pin "2") (pinfunction "S_2") (pintype "passive"))
      (node (ref "R17") (pin "1") (pinfunction "1_1") (pintype "passive"))
      (node (ref "R29") (pin "1") (pinfunction "1_1") (pintype "passive"))
      (node (ref "R41") (pin "1") (pinfunction "1_1") (pintype "passive"))
      (node (ref "TP8") (pin "TP") (pinfunction "TP_TP") (pintype "passive"))
      (node (ref "U3") (pin "2") (pinfunction "VSS_2") (pintype "passive"))
      (node (ref "U4") (pin "2") (pinfunction "VSS_2") (pintype "passive"))
      (node (ref "U5") (pin "2") (pinfunction "VSS_2") (pintype "passive"))
    )
    (net (code "36") (name "Net-(LED3-Pad2)") (class "Default")
      (node (ref "LED3") (pin "2") (pinfunction "2_2") (pintype "passive"))
      (node (ref "R14") (pin "1") (pinfunction "1_1") (pintype "passive"))
    )
    (net (code "37") (name "Net-(LED3-Pad3)") (class "Default")
      (node (ref "LED3") (pin "3") (pinfunction "3_3") (pintype "passive"))
      (node (ref "R11") (pin "1") (pinfunction "1_1") (pintype "passive"))
    )
    (net (code "38") (name "Net-(LED3-Pad4)") (class "Default")
      (node (ref "LED3") (pin "4") (pinfunction "4_4") (pintype "passive"))
      (node (ref "R12") (pin "1") (pinfunction "1_1") (pintype "passive"))
    )
    (net (code "39") (name "Net-(LED4-Pad2)") (class "Default")
      (node (ref "LED4") (pin "2") (pinfunction "2_2") (pintype "passive"))
      (node (ref "R20") (pin "1") (pinfunction "1_1") (pintype "passive"))
    )
    (net (code "40") (name "Net-(LED4-Pad3)") (class "Default")
      (node (ref "LED4") (pin "3") (pinfunction "3_3") (pintype "passive"))
      (node (ref "R18") (pin "1") (pinfunction "1_1") (pintype "passive"))
    )
    (net (code "41") (name "Net-(LED4-Pad4)") (class "Default")
      (node (ref "LED4") (pin "4") (pinfunction "4_4") (pintype "passive"))
      (node (ref "R19") (pin "1") (pinfunction "1_1") (pintype "passive"))
    )
    (net (code "42") (name "Net-(LED5-Pad2)") (class "Default")
      (node (ref "LED5") (pin "2") (pinfunction "2_2") (pintype "passive"))
      (node (ref "R26") (pin "1") (pinfunction "1_1") (pintype "passive"))
    )
    (net (code "43") (name "Net-(LED5-Pad3)") (class "Default")
      (node (ref "LED5") (pin "3") (pinfunction "3_3") (pintype "passive"))
      (node (ref "R23") (pin "1") (pinfunction "1_1") (pintype "passive"))
    )
    (net (code "44") (name "Net-(LED5-Pad4)") (class "Default")
      (node (ref "LED5") (pin "4") (pinfunction "4_4") (pintype "passive"))
      (node (ref "R24") (pin "1") (pinfunction "1_1") (pintype "passive"))
    )
    (net (code "45") (name "Net-(LED6-Pad2)") (class "Default")
      (node (ref "LED6") (pin "2") (pinfunction "2_2") (pintype "passive"))
      (node (ref "R32") (pin "1") (pinfunction "1_1") (pintype "passive"))
    )
    (net (code "46") (name "Net-(LED6-Pad3)") (class "Default")
      (node (ref "LED6") (pin "3") (pinfunction "3_3") (pintype "passive"))
      (node (ref "R30") (pin "1") (pinfunction "1_1") (pintype "passive"))
    )
    (net (code "47") (name "Net-(LED6-Pad4)") (class "Default")
      (node (ref "LED6") (pin "4") (pinfunction "4_4") (pintype "passive"))
      (node (ref "R31") (pin "1") (pinfunction "1_1") (pintype "passive"))
    )
    (net (code "48") (name "Net-(LED7-Pad2)") (class "Default")
      (node (ref "LED7") (pin "2") (pinfunction "2_2") (pintype "passive"))
      (node (ref "R38") (pin "1") (pinfunction "1_1") (pintype "passive"))
    )
    (net (code "49") (name "Net-(LED7-Pad3)") (class "Default")
      (node (ref "LED7") (pin "3") (pinfunction "3_3") (pintype "passive"))
      (node (ref "R35") (pin "1") (pinfunction "1_1") (pintype "passive"))
    )
    (net (code "50") (name "Net-(LED7-Pad4)") (class "Default")
      (node (ref "LED7") (pin "4") (pinfunction "4_4") (pintype "passive"))
      (node (ref "R36") (pin "1") (pinfunction "1_1") (pintype "passive"))
    )
    (net (code "51") (name "Net-(LED8-Pad2)") (class "Default")
      (node (ref "LED8") (pin "2") (pinfunction "2_2") (pintype "passive"))
      (node (ref "R44") (pin "1") (pinfunction "1_1") (pintype "passive"))
    )
    (net (code "52") (name "Net-(LED8-Pad3)") (class "Default")
      (node (ref "LED8") (pin "3") (pinfunction "3_3") (pintype "passive"))
      (node (ref "R42") (pin "1") (pinfunction "1_1") (pintype "passive"))
    )
    (net (code "53") (name "Net-(LED8-Pad4)") (class "Default")
      (node (ref "LED8") (pin "4") (pinfunction "4_4") (pintype "passive"))
      (node (ref "R43") (pin "1") (pinfunction "1_1") (pintype "passive"))
    )
    (net (code "54") (name "Net-(Q2-D)") (class "Default")
      (node (ref "Q2") (pin "3") (pinfunction "D_3") (pintype "passive"))
      (node (ref "R11") (pin "2") (pinfunction "2_2") (pintype "passive"))
      (node (ref "R12") (pin "2") (pinfunction "2_2") (pintype "passive"))
      (node (ref "R14") (pin "2") (pinfunction "2_2") (pintype "passive"))
      (node (ref "R18") (pin "2") (pinfunction "2_2") (pintype "passive"))
      (node (ref "R19") (pin "2") (pinfunction "2_2") (pintype "passive"))
      (node (ref "R20") (pin "2") (pinfunction "2_2") (pintype "passive"))
      (node (ref "TP10") (pin "TP") (pinfunction "TP_TP") (pintype "passive"))
    )
    (net (code "55") (name "Net-(Q2-G)") (class "Default")
      (node (ref "Q2") (pin "1") (pinfunction "G_1") (pintype "passive"))
      (node (ref "R13") (pin "1") (pinfunction "1_1") (pintype "passive"))
      (node (ref "R17") (pin "2") (pinfunction "2_2") (pintype "passive"))
      (node (ref "TP9") (pin "TP") (pinfunction "TP_TP") (pintype "passive"))
    )
    (net (code "56") (name "Net-(Q3-D)") (class "Default")
      (node (ref "Q3") (pin "3") (pinfunction "D_3") (pintype "passive"))
      (node (ref "R23") (pin "2") (pinfunction "2_2") (pintype "passive"))
      (node (ref "R24") (pin "2") (pinfunction "2_2") (pintype "passive"))
      (node (ref "R26") (pin "2") (pinfunction "2_2") (pintype "passive"))
      (node (ref "R30") (pin "2") (pinfunction "2_2") (pintype "passive"))
      (node (ref "R31") (pin "2") (pinfunction "2_2") (pintype "passive"))
      (node (ref "R32") (pin "2") (pinfunction "2_2") (pintype "passive"))
      (node (ref "TP15") (pin "TP") (pinfunction "TP_TP") (pintype "passive"))
    )
    (net (code "57") (name "Net-(Q3-G)") (class "Default")
      (node (ref "Q3") (pin "1") (pinfunction "G_1") (pintype "passive"))
      (node (ref "R25") (pin "1") (pinfunction "1_1") (pintype "passive"))
      (node (ref "R29") (pin "2") (pinfunction "2_2") (pintype "passive"))
      (node (ref "TP14") (pin "TP") (pinfunction "TP_TP") (pintype "passive"))
    )
    (net (code "58") (name "Net-(Q4-D)") (class "Default")
      (node (ref "Q4") (pin "3") (pinfunction "D_3") (pintype "passive"))
      (node (ref "R35") (pin "2") (pinfunction "2_2") (pintype "passive"))
      (node (ref "R36") (pin "2") (pinfunction "2_2") (pintype "passive"))
      (node (ref "R38") (pin "2") (pinfunction "2_2") (pintype "passive"))
      (node (ref "R42") (pin "2") (pinfunction "2_2") (pintype "passive"))
      (node (ref "R43") (pin "2") (pinfunction "2_2") (pintype "passive"))
      (node (ref "R44") (pin "2") (pinfunction "2_2") (pintype "passive"))
      (node (ref "TP20") (pin "TP") (pinfunction "TP_TP") (pintype "passive"))
    )
    (net (code "59") (name "Net-(Q4-G)") (class "Default")
      (node (ref "Q4") (pin "1") (pinfunction "G_1") (pintype "passive"))
      (node (ref "R37") (pin "1") (pinfunction "1_1") (pintype "passive"))
      (node (ref "R41") (pin "2") (pinfunction "2_2") (pintype "passive"))
      (node (ref "TP19") (pin "TP") (pinfunction "TP_TP") (pintype "passive"))
    )
    (net (code "60") (name "VCC3.3") (class "Default")
      (node (ref "C10") (pin "1") (pinfunction "1_1") (pintype "passive"))
      (node (ref "C11") (pin "1") (pinfunction "1_1") (pintype "passive"))
      (node (ref "C15") (pin "1") (pinfunction "1_1") (pintype "passive"))
      (node (ref "C16") (pin "1") (pinfunction "1_1") (pintype "passive"))
      (node (ref "C20") (pin "1") (pinfunction "1_1") (pintype "passive"))
      (node (ref "C21") (pin "1") (pinfunction "1_1") (pintype "passive"))
      (node (ref "J12") (pin "6") (pinfunction "VCC_6") (pintype "passive"))
      (node (ref "J13") (pin "8") (pinfunction "VCC_8") (pintype "passive"))
      (node (ref "J16") (pin "6") (pinfunction "VCC_6") (pintype "passive"))
      (node (ref "J17") (pin "8") (pinfunction "VCC_8") (pintype "passive"))
      (node (ref "J20") (pin "6") (pinfunction "VCC_6") (pintype "passive"))
      (node (ref "J21") (pin "8") (pinfunction "VCC_8") (pintype "passive"))
      (node (ref "R15") (pin "2") (pinfunction "2_2") (pintype "passive"))
      (node (ref "R16") (pin "2") (pinfunction "2_2") (pintype "passive"))
      (node (ref "R27") (pin "2") (pinfunction "2_2") (pintype "passive"))
      (node (ref "R28") (pin "2") (pinfunction "2_2") (pintype "passive"))
      (node (ref "R39") (pin "2") (pinfunction "2_2") (pintype "passive"))
      (node (ref "R40") (pin "2") (pinfunction "2_2") (pintype "passive"))
    )
    (net (code "61") (name "VCCA3.3") (class "Default")
      (node (ref "C12") (pin "1") (pinfunction "1_1") (pintype "passive"))
      (node (ref "C17") (pin "1") (pinfunction "1_1") (pintype "passive"))
      (node (ref "C7") (pin "1") (pinfunction "1_1") (pintype "passive"))
      (node (ref "TP5") (pin "TP") (pinfunction "TP_TP") (pintype "passive"))
      (node (ref "U3") (pin "5") (pinfunction "VDD_5") (pintype "passive"))
      (node (ref "U4") (pin "5") (pinfunction "VDD_5") (pintype "passive"))
      (node (ref "U5") (pin "5") (pinfunction "VDD_5") (pintype "passive"))
    )
  )
)
